# Modular_Bluetooth_Receiver.net
KiCad netlist of a schematic drawn in EAGLE
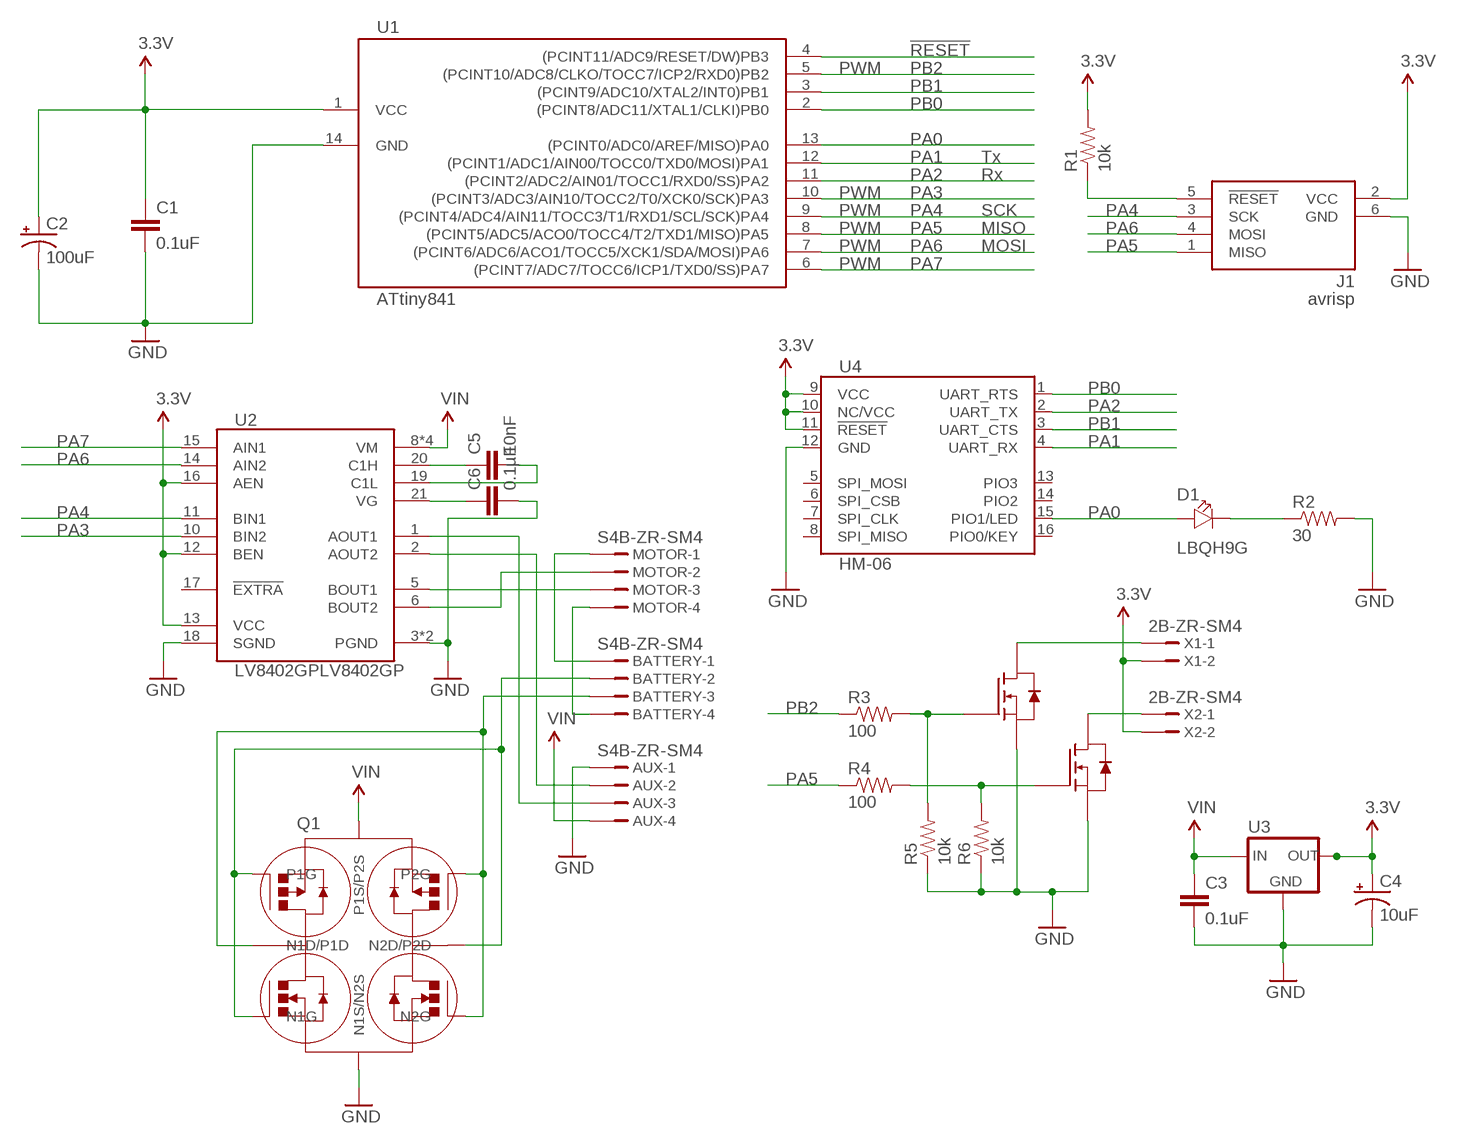
[diagram p0: schematic, sheet 1]

(export (version "E")
  (design (tool "Eeschema 10.0.6"))
  (components
    (comp (ref "AUX")
      (value "S4B-ZR-SM4")
      (footprint "eagle-import:S4B-ZR-SM4")
      (fields (field (name "MF") "FARNELL") (field (name "MPN") "S4B-ZR(LF)(SN)"))
      (libsource (lib "eagle-import") (part "?4B-ZR-SM4S"))
    )
    (comp (ref "BATTERY")
      (value "S4B-ZR-SM4")
      (footprint "eagle-import:S4B-ZR-SM4")
      (fields (field (name "MF") "FARNELL") (field (name "MPN") "S4B-ZR(LF)(SN)"))
      (libsource (lib "eagle-import") (part "?4B-ZR-SM4S"))
    )
    (comp (ref "C1")
      (value "0.1uF")
      (footprint "eagle-import:0402")
      (fields (field (name "PARTNO") "0603YC104KAT2A"))
      (libsource (lib "eagle-import") (part "C0402"))
    )
    (comp (ref "C2")
      (value "100uF")
      (footprint "eagle-import:1206")
      (fields (field (name "PARTNO") "MCTT21X106M6R3CT"))
      (libsource (lib "eagle-import") (part "C_POL"))
    )
    (comp (ref "C3")
      (value "0.1uF")
      (footprint "eagle-import:0402")
      (libsource (lib "eagle-import") (part "C0402"))
    )
    (comp (ref "C4")
      (value "10uF")
      (footprint "eagle-import:1206")
      (libsource (lib "eagle-import") (part "C_POL"))
    )
    (comp (ref "C5")
      (value "10nF")
      (footprint "eagle-import:0402")
      (libsource (lib "eagle-import") (part "C0402"))
    )
    (comp (ref "C6")
      (value "0.1µF")
      (footprint "eagle-import:0402")
      (libsource (lib "eagle-import") (part "C0402"))
    )
    (comp (ref "D1")
      (value "LBQH9G")
      (footprint "eagle-import:0402_POL")
      (libsource (lib "eagle-import") (part "LED"))
    )
    (comp (ref "J1")
      (value "avrisp")
      (footprint "eagle-import:CON6P2R")
      (libsource (lib "eagle-import") (part "AVRISP6_COMPACT"))
    )
    (comp (ref "MOTOR")
      (value "S4B-ZR-SM4")
      (footprint "eagle-import:S4B-ZR-SM4")
      (fields (field (name "MF") "FARNELL") (field (name "MPN") "S4B-ZR(LF)(SN)"))
      (libsource (lib "eagle-import") (part "?4B-ZR-SM4S"))
    )
    (comp (ref "Q1")
      (value "DMHC3025LSD-13")
      (footprint "eagle-import:SO8")
      (libsource (lib "eagle-import") (part "IC_FET_BRIDGESO8"))
    )
    (comp (ref "Q2")
      (value "DMN32D2LV")
      (footprint "eagle-import:SOT-563")
      (libsource (lib "eagle-import") (part "DMN32D2LV"))
    )
    (comp (ref "R1")
      (value "10k")
      (footprint "eagle-import:0402")
      (fields (field (name "PARTNO") "ERJ-3GEYJ103V"))
      (libsource (lib "eagle-import") (part "R0402"))
    )
    (comp (ref "R2")
      (value "30")
      (footprint "eagle-import:0402")
      (libsource (lib "eagle-import") (part "R0402"))
    )
    (comp (ref "R3")
      (value "100")
      (footprint "eagle-import:0402")
      (libsource (lib "eagle-import") (part "R0402"))
    )
    (comp (ref "R4")
      (value "100")
      (footprint "eagle-import:0402")
      (libsource (lib "eagle-import") (part "R0402"))
    )
    (comp (ref "R5")
      (value "10k")
      (footprint "eagle-import:0402")
      (fields (field (name "PARTNO") "ERJ-3GEYJ103V"))
      (libsource (lib "eagle-import") (part "R0402"))
    )
    (comp (ref "R6")
      (value "10k")
      (footprint "eagle-import:0402")
      (fields (field (name "PARTNO") "ERJ-3GEYJ103V"))
      (libsource (lib "eagle-import") (part "R0402"))
    )
    (comp (ref "U1")
      (value "ATtiny841")
      (footprint "eagle-import:14SOICN")
      (libsource (lib "eagle-import") (part "ATTINY441/841-SSU"))
    )
    (comp (ref "U2")
      (value "LV8402GPLV8402GP")
      (footprint "eagle-import:VCT24")
      (libsource (lib "eagle-import") (part "LV8402GPLV8402GP"))
    )
    (comp (ref "U3")
      (value "RT9164A")
      (footprint "eagle-import:SOT223")
      (libsource (lib "eagle-import") (part "IC_RT9164A"))
    )
    (comp (ref "U4")
      (value "HM-06")
      (footprint "eagle-import:HM-05_06_07")
      (libsource (lib "eagle-import") (part "HM-05/06/07HM-05/06/07"))
    )
    (comp (ref "X1")
      (value "2B-ZR-SM4")
      (footprint "eagle-import:S2B-ZR-SM4")
      (libsource (lib "eagle-import") (part "?2B-ZR-SM4"))
    )
    (comp (ref "X2")
      (value "2B-ZR-SM4")
      (footprint "eagle-import:S2B-ZR-SM4")
      (libsource (lib "eagle-import") (part "?2B-ZR-SM4"))
    )
  )
  (nets
    (net (code "1") (name "/PA0") (class "Default")
      (node (ref "D1") (pin "P$2") (pinfunction "P$1_P$2") (pintype "input"))
      (node (ref "U1") (pin "13") (pinfunction "(PCINT0/ADC0/AREF/MISO)PA0_13") (pintype "bidirectional"))
      (node (ref "U4") (pin "15") (pinfunction "PIO1/LED_15") (pintype "bidirectional"))
    )
    (net (code "2") (name "/PA1") (class "Default")
      (node (ref "U1") (pin "12") (pinfunction "(PCINT1/ADC1/AIN00/TOCC0/TXD0/MOSI)PA1_12") (pintype "bidirectional"))
      (node (ref "U4") (pin "4") (pinfunction "UART_RX_4") (pintype "bidirectional"))
    )
    (net (code "3") (name "/PA2") (class "Default")
      (node (ref "U1") (pin "11") (pinfunction "(PCINT2/ADC2/AIN01/TOCC1/RXD0/SS)PA2_11") (pintype "bidirectional"))
      (node (ref "U4") (pin "2") (pinfunction "UART_TX_2") (pintype "bidirectional"))
    )
    (net (code "4") (name "/PA3") (class "Default")
      (node (ref "U1") (pin "10") (pinfunction "(PCINT3/ADC3/AIN10/TOCC2/T0/XCK0/SCK)PA3_10") (pintype "bidirectional"))
      (node (ref "U2") (pin "10") (pinfunction "BIN2_10") (pintype "bidirectional"))
    )
    (net (code "5") (name "/PA4") (class "Default")
      (node (ref "J1") (pin "3") (pinfunction "SCK_3") (pintype "output"))
      (node (ref "U1") (pin "9") (pinfunction "(PCINT4/ADC4/AIN11/TOCC3/T1/RXD1/SCL/SCK)PA4_9") (pintype "bidirectional"))
      (node (ref "U2") (pin "11") (pinfunction "BIN1_11") (pintype "bidirectional"))
    )
    (net (code "6") (name "/PA5") (class "Default")
      (node (ref "J1") (pin "1") (pinfunction "MISO_1") (pintype "input"))
      (node (ref "R4") (pin "1") (pinfunction "1_1") (pintype "passive"))
      (node (ref "U1") (pin "8") (pinfunction "(PCINT5/ADC5/ACO0/TOCC4/T2/TXD1/MISO)PA5_8") (pintype "bidirectional"))
    )
    (net (code "7") (name "/PA6") (class "Default")
      (node (ref "J1") (pin "4") (pinfunction "MOSI_4") (pintype "output"))
      (node (ref "U1") (pin "7") (pinfunction "(PCINT6/ADC6/ACO1/TOCC5/XCK1/SDA/MOSI)PA6_7") (pintype "bidirectional"))
      (node (ref "U2") (pin "14") (pinfunction "AIN2_14") (pintype "bidirectional"))
    )
    (net (code "8") (name "/PA7") (class "Default")
      (node (ref "U1") (pin "6") (pinfunction "(PCINT7/ADC7/TOCC6/ICP1/TXD0/SS)PA7_6") (pintype "bidirectional"))
      (node (ref "U2") (pin "15") (pinfunction "AIN1_15") (pintype "bidirectional"))
    )
    (net (code "9") (name "/PB0") (class "Default")
      (node (ref "U1") (pin "2") (pinfunction "(PCINT8/ADC11/XTAL1/CLKI)PB0_2") (pintype "bidirectional"))
      (node (ref "U4") (pin "1") (pinfunction "UART_RTS_1") (pintype "bidirectional"))
    )
    (net (code "10") (name "/PB1") (class "Default")
      (node (ref "U1") (pin "3") (pinfunction "(PCINT9/ADC10/XTAL2/INT0)PB1_3") (pintype "bidirectional"))
      (node (ref "U4") (pin "3") (pinfunction "UART_CTS_3") (pintype "bidirectional"))
    )
    (net (code "11") (name "/PB2") (class "Default")
      (node (ref "R3") (pin "1") (pinfunction "1_1") (pintype "passive"))
      (node (ref "U1") (pin "5") (pinfunction "(PCINT10/ADC8/CLKO/TOCC7/ICP2/RXD0)PB2_5") (pintype "bidirectional"))
    )
    (net (code "12") (name "/~{RESET}") (class "Default")
      (node (ref "J1") (pin "5") (pinfunction "~{RESET}_5") (pintype "output"))
      (node (ref "R1") (pin "1") (pinfunction "1_1") (pintype "passive"))
      (node (ref "U1") (pin "4") (pinfunction "(PCINT11/ADC9/RESET/DW)PB3_4") (pintype "bidirectional"))
    )
    (net (code "13") (name "3.3V") (class "Default")
      (node (ref "C1") (pin "1") (pinfunction "1_1") (pintype "passive"))
      (node (ref "C2") (pin "1") (pinfunction "+_1") (pintype "passive"))
      (node (ref "C4") (pin "1") (pinfunction "+_1") (pintype "passive"))
      (node (ref "J1") (pin "2") (pinfunction "VCC_2") (pintype "power_in"))
      (node (ref "R1") (pin "2") (pinfunction "2_2") (pintype "passive"))
      (node (ref "U1") (pin "1") (pinfunction "VCC_1") (pintype "bidirectional"))
      (node (ref "U2") (pin "12") (pinfunction "BEN_12") (pintype "bidirectional"))
      (node (ref "U2") (pin "13") (pinfunction "VCC_13") (pintype "bidirectional"))
      (node (ref "U2") (pin "16") (pinfunction "AEN_16") (pintype "bidirectional"))
      (node (ref "U3") (pin "2") (pinfunction "OUT_2") (pintype "output"))
      (node (ref "U3") (pin "4") (pinfunction "OUT_4") (pintype "output"))
      (node (ref "U4") (pin "10") (pinfunction "NC/VCC_10") (pintype "bidirectional"))
      (node (ref "U4") (pin "11") (pinfunction "~{RESET}_11") (pintype "bidirectional"))
      (node (ref "U4") (pin "9") (pinfunction "VCC_9") (pintype "bidirectional"))
      (node (ref "X1") (pin "2") (pinfunction "1_2") (pintype "passive"))
      (node (ref "X2") (pin "2") (pinfunction "1_2") (pintype "passive"))
    )
    (net (code "14") (name "GND") (class "Default")
      (node (ref "AUX") (pin "1") (pinfunction "1_1") (pintype "passive"))
      (node (ref "C1") (pin "2") (pinfunction "2_2") (pintype "passive"))
      (node (ref "C2") (pin "2") (pinfunction "-_2") (pintype "passive"))
      (node (ref "C3") (pin "2") (pinfunction "2_2") (pintype "passive"))
      (node (ref "C4") (pin "2") (pinfunction "-_2") (pintype "passive"))
      (node (ref "C6") (pin "2") (pinfunction "2_2") (pintype "passive"))
      (node (ref "J1") (pin "6") (pinfunction "GND_6") (pintype "power_in"))
      (node (ref "Q1") (pin "P$3") (pinfunction "N1S/N2S_P$3") (pintype "bidirectional"))
      (node (ref "Q2") (pin "P$1") (pinfunction "SOURCE_P$1") (pintype "bidirectional"))
      (node (ref "Q2") (pin "P$4") (pinfunction "SOURCE_P$4") (pintype "bidirectional"))
      (node (ref "R2") (pin "2") (pinfunction "2_2") (pintype "passive"))
      (node (ref "R5") (pin "1") (pinfunction "1_1") (pintype "passive"))
      (node (ref "R6") (pin "1") (pinfunction "1_1") (pintype "passive"))
      (node (ref "U1") (pin "14") (pinfunction "GND_14") (pintype "bidirectional"))
      (node (ref "U2") (pin "18") (pinfunction "SGND_18") (pintype "bidirectional"))
      (node (ref "U2") (pin "3") (pinfunction "PGND_3") (pintype "bidirectional"))
      (node (ref "U2") (pin "4") (pinfunction "PGND_4") (pintype "bidirectional"))
      (node (ref "U3") (pin "1") (pinfunction "GND_1") (pintype "input"))
      (node (ref "U4") (pin "12") (pinfunction "GND_12") (pintype "bidirectional"))
    )
    (net (code "15") (name "Net-(AUXB-1)") (class "Default")
      (node (ref "AUX") (pin "2") (pinfunction "1_2") (pintype "passive"))
      (node (ref "U2") (pin "2") (pinfunction "AOUT2_2") (pintype "bidirectional"))
    )
    (net (code "16") (name "Net-(AUXC-1)") (class "Default")
      (node (ref "AUX") (pin "3") (pinfunction "1_3") (pintype "passive"))
      (node (ref "U2") (pin "1") (pinfunction "AOUT1_1") (pintype "bidirectional"))
    )
    (net (code "17") (name "Net-(BATTERY-Pad1)") (class "Default")
      (node (ref "BATTERY") (pin "1") (pinfunction "1_1") (pintype "passive"))
      (node (ref "MOTOR") (pin "1") (pinfunction "1_1") (pintype "passive"))
    )
    (net (code "18") (name "Net-(BATTERYB-1)") (class "Default")
      (node (ref "BATTERY") (pin "2") (pinfunction "1_2") (pintype "passive"))
      (node (ref "Q1") (pin "P$1") (pinfunction "N1G_P$1") (pintype "bidirectional"))
      (node (ref "Q1") (pin "P$6") (pinfunction "N2D/P2D_P$6") (pintype "bidirectional"))
      (node (ref "Q1") (pin "P$8") (pinfunction "P1G_P$8") (pintype "bidirectional"))
    )
    (net (code "19") (name "Net-(BATTERYC-1)") (class "Default")
      (node (ref "BATTERY") (pin "3") (pinfunction "1_3") (pintype "passive"))
      (node (ref "Q1") (pin "P$2") (pinfunction "N1D/P1D_P$2") (pintype "bidirectional"))
      (node (ref "Q1") (pin "P$4") (pinfunction "N2G_P$4") (pintype "bidirectional"))
      (node (ref "Q1") (pin "P$5") (pinfunction "P2G_P$5") (pintype "bidirectional"))
    )
    (net (code "20") (name "Net-(BATTERYD-1)") (class "Default")
      (node (ref "BATTERY") (pin "4") (pinfunction "1_4") (pintype "passive"))
      (node (ref "MOTOR") (pin "4") (pinfunction "1_4") (pintype "passive"))
    )
    (net (code "21") (name "Net-(D1-P$2)") (class "Default")
      (node (ref "D1") (pin "P$1") (pinfunction "P$2_P$1") (pintype "output"))
      (node (ref "R2") (pin "1") (pinfunction "1_1") (pintype "passive"))
    )
    (net (code "22") (name "Net-(MOTORB-1)") (class "Default")
      (node (ref "MOTOR") (pin "2") (pinfunction "1_2") (pintype "passive"))
      (node (ref "U2") (pin "6") (pinfunction "BOUT2_6") (pintype "bidirectional"))
    )
    (net (code "23") (name "Net-(MOTORC-1)") (class "Default")
      (node (ref "MOTOR") (pin "3") (pinfunction "1_3") (pintype "passive"))
      (node (ref "U2") (pin "5") (pinfunction "BOUT1_5") (pintype "bidirectional"))
    )
    (net (code "24") (name "Net-(Q2A-DRAIN)") (class "Default")
      (node (ref "Q2") (pin "P$6") (pinfunction "DRAIN_P$6") (pintype "bidirectional"))
      (node (ref "X1") (pin "1") (pinfunction "1_1") (pintype "passive"))
    )
    (net (code "25") (name "Net-(Q2A-GATE)") (class "Default")
      (node (ref "Q2") (pin "P$2") (pinfunction "GATE_P$2") (pintype "bidirectional"))
      (node (ref "R3") (pin "2") (pinfunction "2_2") (pintype "passive"))
      (node (ref "R5") (pin "2") (pinfunction "2_2") (pintype "passive"))
    )
    (net (code "26") (name "Net-(Q2B-DRAIN)") (class "Default")
      (node (ref "Q2") (pin "P$3") (pinfunction "DRAIN_P$3") (pintype "bidirectional"))
      (node (ref "X2") (pin "1") (pinfunction "1_1") (pintype "passive"))
    )
    (net (code "27") (name "Net-(Q2B-GATE)") (class "Default")
      (node (ref "Q2") (pin "P$5") (pinfunction "GATE_P$5") (pintype "bidirectional"))
      (node (ref "R4") (pin "2") (pinfunction "2_2") (pintype "passive"))
      (node (ref "R6") (pin "2") (pinfunction "2_2") (pintype "passive"))
    )
    (net (code "28") (name "Net-(U2-C1H)") (class "Default")
      (node (ref "C5") (pin "1") (pinfunction "1_1") (pintype "passive"))
      (node (ref "U2") (pin "20") (pinfunction "C1H_20") (pintype "bidirectional"))
    )
    (net (code "29") (name "Net-(U2-C1L)") (class "Default")
      (node (ref "C5") (pin "2") (pinfunction "2_2") (pintype "passive"))
      (node (ref "U2") (pin "19") (pinfunction "C1L_19") (pintype "bidirectional"))
    )
    (net (code "30") (name "Net-(U2-VG)") (class "Default")
      (node (ref "C6") (pin "1") (pinfunction "1_1") (pintype "passive"))
      (node (ref "U2") (pin "21") (pinfunction "VG_21") (pintype "bidirectional"))
    )
    (net (code "31") (name "VIN") (class "Default")
      (node (ref "AUX") (pin "4") (pinfunction "1_4") (pintype "passive"))
      (node (ref "C3") (pin "1") (pinfunction "1_1") (pintype "passive"))
      (node (ref "Q1") (pin "P$7") (pinfunction "P1S/P2S_P$7") (pintype "bidirectional"))
      (node (ref "U2") (pin "22") (pinfunction "VM_22") (pintype "bidirectional"))
      (node (ref "U2") (pin "23") (pinfunction "VM_23") (pintype "bidirectional"))
      (node (ref "U2") (pin "8") (pinfunction "VM_8") (pintype "bidirectional"))
      (node (ref "U2") (pin "9") (pinfunction "VM_9") (pintype "bidirectional"))
      (node (ref "U3") (pin "3") (pinfunction "IN_3") (pintype "input"))
    )
    (net (code "32") (name "unconnected-(U2-~{EXTRA}-Pad17)") (class "Default")
      (node (ref "U2") (pin "17") (pinfunction "~{EXTRA}_17") (pintype "bidirectional"))
    )
    (net (code "33") (name "unconnected-(U4-PIO0{slash}KEY-Pad16)") (class "Default")
      (node (ref "U4") (pin "16") (pinfunction "PIO0/KEY_16") (pintype "bidirectional"))
    )
    (net (code "34") (name "unconnected-(U4-PIO2-Pad14)") (class "Default")
      (node (ref "U4") (pin "14") (pinfunction "PIO2_14") (pintype "bidirectional"))
    )
    (net (code "35") (name "unconnected-(U4-PIO3-Pad13)") (class "Default")
      (node (ref "U4") (pin "13") (pinfunction "PIO3_13") (pintype "bidirectional"))
    )
    (net (code "36") (name "unconnected-(U4-SPI_CLK-Pad7)") (class "Default")
      (node (ref "U4") (pin "7") (pinfunction "SPI_CLK_7") (pintype "bidirectional"))
    )
    (net (code "37") (name "unconnected-(U4-SPI_CSB-Pad6)") (class "Default")
      (node (ref "U4") (pin "6") (pinfunction "SPI_CSB_6") (pintype "bidirectional"))
    )
    (net (code "38") (name "unconnected-(U4-SPI_MISO-Pad8)") (class "Default")
      (node (ref "U4") (pin "8") (pinfunction "SPI_MISO_8") (pintype "bidirectional"))
    )
    (net (code "39") (name "unconnected-(U4-SPI_MOSI-Pad5)") (class "Default")
      (node (ref "U4") (pin "5") (pinfunction "SPI_MOSI_5") (pintype "bidirectional"))
    )
  )
)
